# USB_TO_UART_CONVERTER.net
KiCad netlist of a schematic drawn in Altium Designer
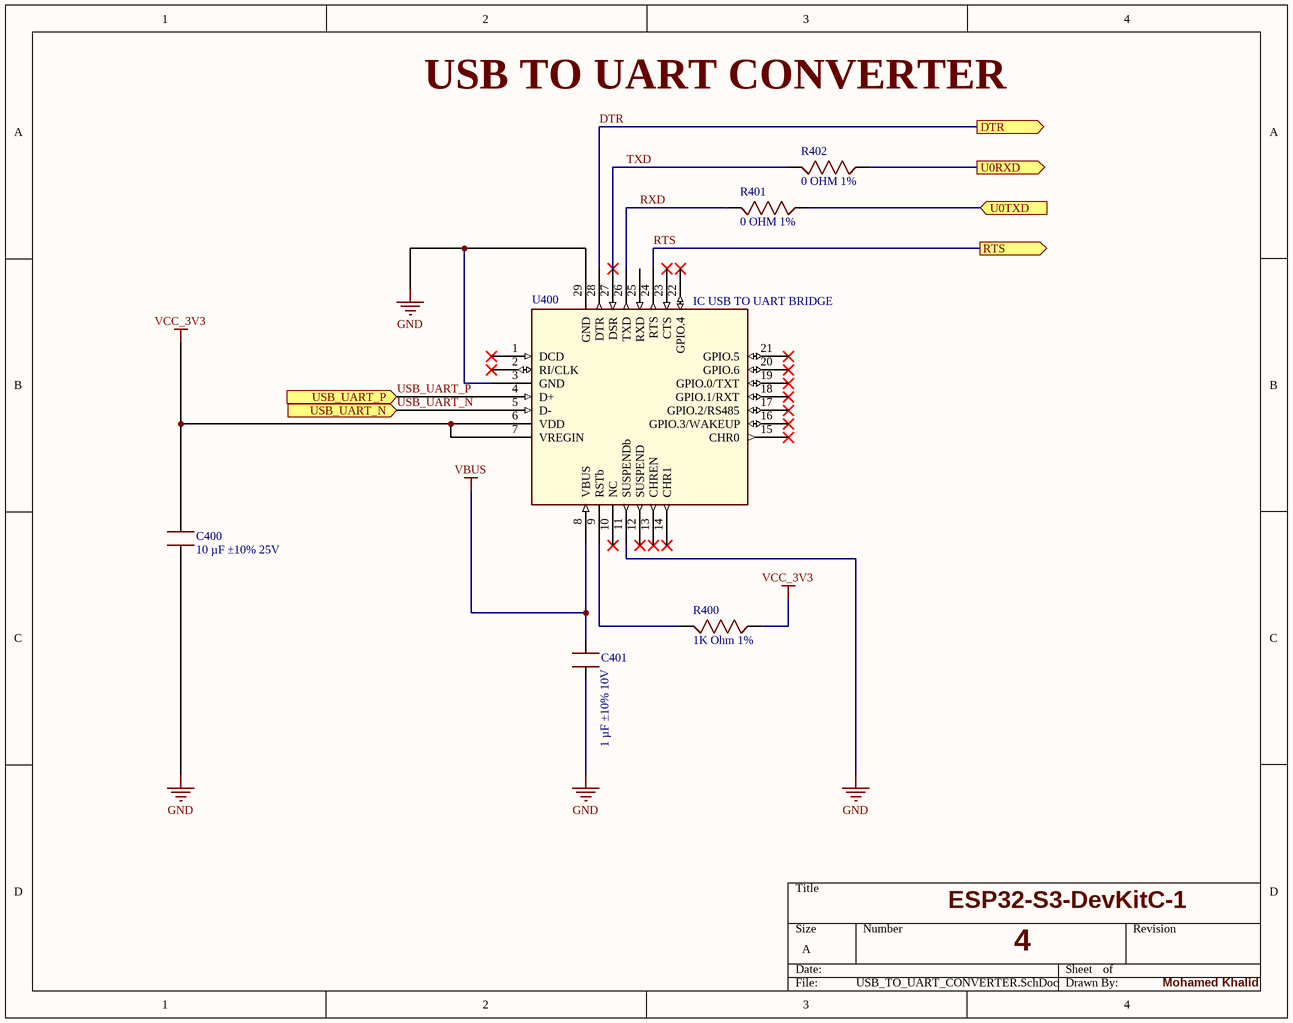
[diagram p0: USB_TO_UART_CONVERTER.SchDoc]

(export (version "E")
  (design (tool "Eeschema 10.0.6"))
  (components
    (comp (ref "C400")
      (value "10 µF ±10% 25V")
      (footprint "CAPC2012X145N")
      (description "10 µF ±10% 25V Ceramic Capacitor X5R 0805 (2012 Metric)")
      (fields (field (name "TOLERANCE") "±10%"))
      (libsource (lib "Schlib") (part "CL21A106KAYNNNE"))
    )
    (comp (ref "C401")
      (value "1 µF ±10% 10V")
      (footprint "CAPC1608X90N")
      (description "1 µF ±10% 10V Ceramic Capacitor X7R 0603 (1608 Metric)")
      (fields (field (name "TOLERANCE") "±10%"))
      (libsource (lib "ESP32_Integrated_Library") (part "CL10B105KP8NNNC"))
    )
    (comp (ref "R400")
      (value "1K Ohm 1%")
      (footprint "RESC2012X65N")
      (description "1 kOhms ±1% 0.125W, 1/8W Chip Resistor 0805 (2012 Metric) Automotive AEC-Q200 Thick Film")
      (fields (field (name "TOLERANCE") "± 1%"))
      (libsource (lib "ESP32_Integrated_Library") (part "RMCF0805FT1K00"))
    )
    (comp (ref "R401")
      (value "0 OHM 1%")
      (footprint "RESC2012X65N")
      (description "10 kOhms ±1% 0.125W, 1/8W Chip Resistor 0805 (2012 Metric) Automotive AEC-Q200 Thick Film")
      (fields (field (name "TOLERANCE") "±1%"))
      (libsource (lib "ESP32_Integrated_Library") (part "RMCF0805FT10K0"))
    )
    (comp (ref "R402")
      (value "0 OHM 1%")
      (footprint "RESC2012X65N")
      (description "10 kOhms ±1% 0.125W, 1/8W Chip Resistor 0805 (2012 Metric) Automotive AEC-Q200 Thick Film")
      (fields (field (name "TOLERANCE") "±1%"))
      (libsource (lib "ESP32_Integrated_Library") (part "RMCF0805FT10K0"))
    )
    (comp (ref "U400")
      (value "IC USB TO UART BRIDGE")
      (footprint "QFN28_5X5_SIL")
      (description "USB Bridge, USB to UART USB 2.0 UART Interface 28-QFN (5x5)")
      (libsource (lib "ESP32_Integrated_Library") (part "CP2102N-A02-GQFN28"))
    )
  )
  (nets
    (net (code "1") (name "/DTR") (class "Default")
      (node (ref "U400") (pin "28") (pinfunction "DTR_28") (pintype "output"))
    )
    (net (code "2") (name "/RTS") (class "Default")
      (node (ref "U400") (pin "24") (pinfunction "RTS_24") (pintype "output"))
    )
    (net (code "3") (name "/RXD") (class "Default")
      (node (ref "R401") (pin "1") (pinfunction "1_1") (pintype "passive"))
      (node (ref "U400") (pin "26") (pinfunction "TXD_26") (pintype "output"))
    )
    (net (code "4") (name "/TXD") (class "Default")
      (node (ref "R402") (pin "1") (pinfunction "1_1") (pintype "passive"))
      (node (ref "U400") (pin "27") (pinfunction "DSR_27") (pintype "input"))
    )
    (net (code "5") (name "/U0RXD") (class "Default")
      (node (ref "R402") (pin "2") (pinfunction "2_2") (pintype "passive"))
    )
    (net (code "6") (name "/U0TXD") (class "Default")
      (node (ref "R401") (pin "2") (pinfunction "2_2") (pintype "passive"))
    )
    (net (code "7") (name "/USB_UART_N") (class "Default")
      (node (ref "U400") (pin "5") (pinfunction "D-_5") (pintype "input"))
    )
    (net (code "8") (name "/USB_UART_P") (class "Default")
      (node (ref "U400") (pin "4") (pinfunction "D+_4") (pintype "input"))
    )
    (net (code "9") (name "GND") (class "Default")
      (node (ref "C400") (pin "1") (pinfunction "1_1") (pintype "passive"))
      (node (ref "C401") (pin "1") (pinfunction "1_1") (pintype "passive"))
      (node (ref "U400") (pin "11") (pinfunction "SUSPENDb_11") (pintype "output"))
      (node (ref "U400") (pin "29") (pinfunction "GND_29") (pintype "passive"))
      (node (ref "U400") (pin "3") (pinfunction "GND_3") (pintype "passive"))
    )
    (net (code "10") (name "Net-(U400-RSTb)") (class "Default")
      (node (ref "R400") (pin "1") (pinfunction "1_1") (pintype "passive"))
      (node (ref "U400") (pin "9") (pinfunction "RSTb_9") (pintype "passive"))
    )
    (net (code "11") (name "VBUS") (class "Default")
      (node (ref "C401") (pin "2") (pinfunction "2_2") (pintype "passive"))
      (node (ref "U400") (pin "8") (pinfunction "VBUS_8") (pintype "input"))
    )
    (net (code "12") (name "VCC_3V3") (class "Default")
      (node (ref "C400") (pin "2") (pinfunction "2_2") (pintype "passive"))
      (node (ref "R400") (pin "2") (pinfunction "2_2") (pintype "passive"))
      (node (ref "U400") (pin "6") (pinfunction "VDD_6") (pintype "power_in"))
      (node (ref "U400") (pin "7") (pinfunction "VREGIN_7") (pintype "power_in"))
    )
    (net (code "13") (name "unconnected-(U400-CHR0-Pad15)") (class "Default")
      (node (ref "U400") (pin "15") (pinfunction "CHR0_15") (pintype "output+no_connect"))
    )
    (net (code "14") (name "unconnected-(U400-CHR1-Pad14)") (class "Default")
      (node (ref "U400") (pin "14") (pinfunction "CHR1_14") (pintype "output+no_connect"))
    )
    (net (code "15") (name "unconnected-(U400-CHREN-Pad13)") (class "Default")
      (node (ref "U400") (pin "13") (pinfunction "CHREN_13") (pintype "output+no_connect"))
    )
    (net (code "16") (name "unconnected-(U400-CTS-Pad23)") (class "Default")
      (node (ref "U400") (pin "23") (pinfunction "CTS_23") (pintype "input+no_connect"))
    )
    (net (code "17") (name "unconnected-(U400-DCD-Pad1)") (class "Default")
      (node (ref "U400") (pin "1") (pinfunction "DCD_1") (pintype "input+no_connect"))
    )
    (net (code "18") (name "unconnected-(U400-GPIO.0{slash}TXT-Pad19)") (class "Default")
      (node (ref "U400") (pin "19") (pinfunction "GPIO.0/TXT_19") (pintype "bidirectional+no_connect"))
    )
    (net (code "19") (name "unconnected-(U400-GPIO.1{slash}RXT-Pad18)") (class "Default")
      (node (ref "U400") (pin "18") (pinfunction "GPIO.1/RXT_18") (pintype "bidirectional+no_connect"))
    )
    (net (code "20") (name "unconnected-(U400-GPIO.2{slash}RS485-Pad17)") (class "Default")
      (node (ref "U400") (pin "17") (pinfunction "GPIO.2/RS485_17") (pintype "bidirectional+no_connect"))
    )
    (net (code "21") (name "unconnected-(U400-GPIO.3{slash}WAKEUP-Pad16)") (class "Default")
      (node (ref "U400") (pin "16") (pinfunction "GPIO.3/WAKEUP_16") (pintype "bidirectional+no_connect"))
    )
    (net (code "22") (name "unconnected-(U400-GPIO.4-Pad22)") (class "Default")
      (node (ref "U400") (pin "22") (pinfunction "GPIO.4_22") (pintype "bidirectional+no_connect"))
    )
    (net (code "23") (name "unconnected-(U400-GPIO.5-Pad21)") (class "Default")
      (node (ref "U400") (pin "21") (pinfunction "GPIO.5_21") (pintype "bidirectional+no_connect"))
    )
    (net (code "24") (name "unconnected-(U400-GPIO.6-Pad20)") (class "Default")
      (node (ref "U400") (pin "20") (pinfunction "GPIO.6_20") (pintype "bidirectional+no_connect"))
    )
    (net (code "25") (name "unconnected-(U400-NC-Pad10)") (class "Default")
      (node (ref "U400") (pin "10") (pinfunction "NC_10") (pintype "passive+no_connect"))
    )
    (net (code "26") (name "unconnected-(U400-RI{slash}CLK-Pad2)") (class "Default")
      (node (ref "U400") (pin "2") (pinfunction "RI/CLK_2") (pintype "bidirectional+no_connect"))
    )
    (net (code "27") (name "unconnected-(U400-RXD-Pad25)") (class "Default")
      (node (ref "U400") (pin "25") (pinfunction "RXD_25") (pintype "input"))
    )
    (net (code "28") (name "unconnected-(U400-SUSPEND-Pad12)") (class "Default")
      (node (ref "U400") (pin "12") (pinfunction "SUSPEND_12") (pintype "output+no_connect"))
    )
  )
)
